# Neon_Fader_V2_v376.net
KiCad netlist of a schematic drawn in EAGLE
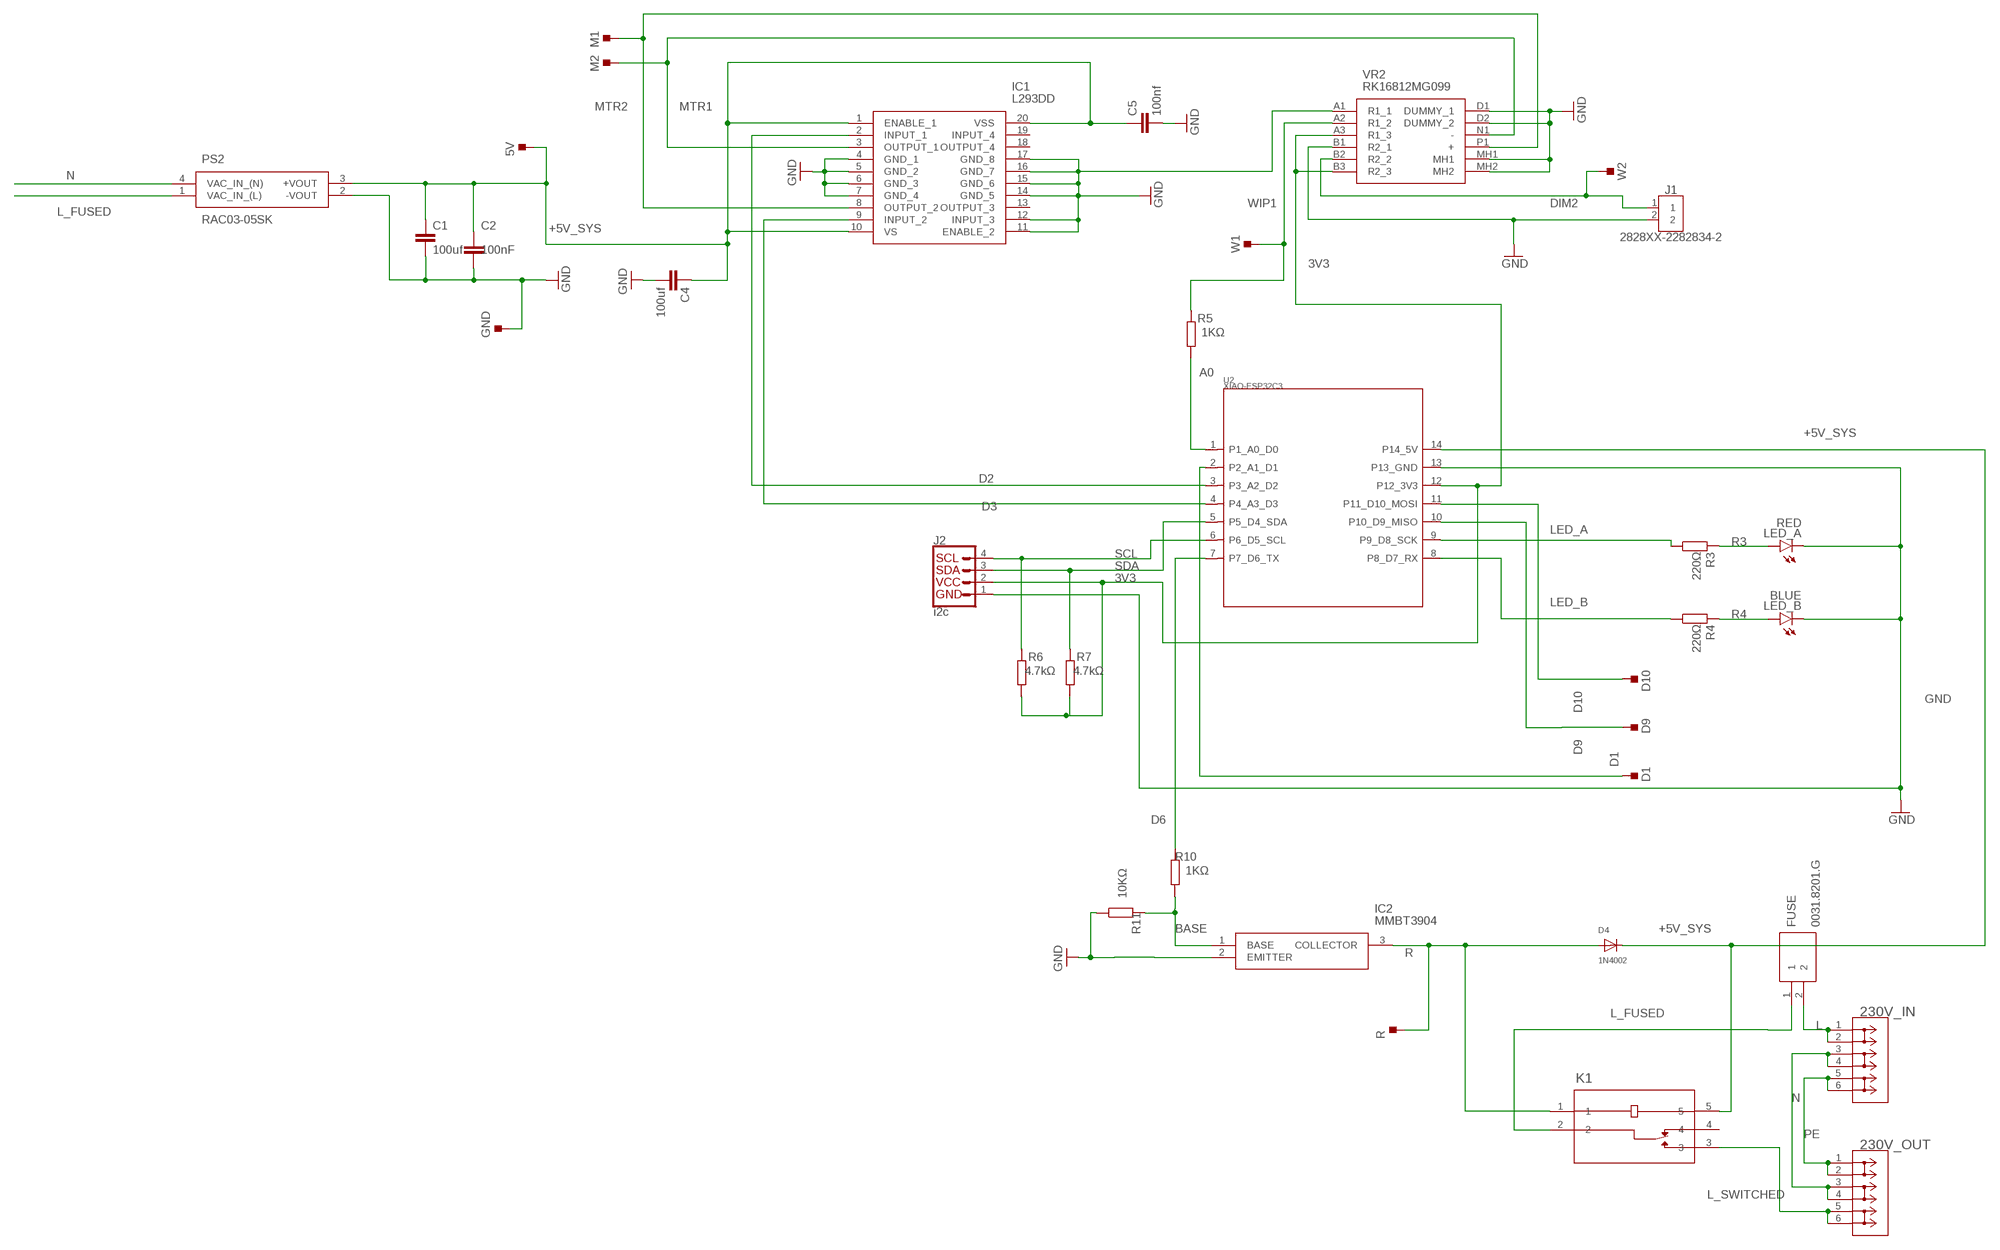
[diagram p0: schematic, sheet 1]

(export (version "E")
  (design (tool "Eeschema 10.0.6"))
  (components
    (comp (ref "5V")
      (value "TESTPOINT_TPS-PAD-036")
      (footprint "eagle-import:TESTPOINT_PAD-036")
      (libsource (lib "eagle-import") (part "TESTPOINT_TPS-PAD-036"))
    )
    (comp (ref "230V_IN")
      (value "2604-1103CONN3_2604-1103_WAG")
      (footprint "eagle-import:CONN3_2604-1103_WAG")
      (fields
        (field (name "MANUFACTURER_PART_NUMBER") "2604-1103")
        (field (name "COPYRIGHT") "Copyright (C) 2026 Ultra Librarian. All rights reserved.")
      )
      (libsource (lib "eagle-import") (part "2604-1103CONN3_2604-1103_WAG"))
    )
    (comp (ref "230V_OUT")
      (value "2604-1103CONN3_2604-1103_WAG")
      (footprint "eagle-import:CONN3_2604-1103_WAG")
      (fields
        (field (name "MANUFACTURER_PART_NUMBER") "2604-1103")
        (field (name "COPYRIGHT") "Copyright (C) 2026 Ultra Librarian. All rights reserved.")
      )
      (libsource (lib "eagle-import") (part "2604-1103CONN3_2604-1103_WAG"))
    )
    (comp (ref "C1")
      (value "100uf")
      (footprint "eagle-import:C1210")
      (libsource (lib "eagle-import") (part "C-EUC1210"))
    )
    (comp (ref "C2")
      (value "100nF")
      (footprint "eagle-import:C0402")
      (libsource (lib "eagle-import") (part "C-EUC0402"))
    )
    (comp (ref "C4")
      (value "100uf")
      (footprint "eagle-import:C1210")
      (libsource (lib "eagle-import") (part "C-EUC1210"))
    )
    (comp (ref "C5")
      (value "100nf")
      (footprint "eagle-import:C0402")
      (libsource (lib "eagle-import") (part "C-EUC0402"))
    )
    (comp (ref "D1")
      (value "TESTPOINT_TPS-PAD-036")
      (footprint "eagle-import:TESTPOINT_PAD-036")
      (libsource (lib "eagle-import") (part "TESTPOINT_TPS-PAD-036"))
    )
    (comp (ref "D4")
      (value "1N4002")
      (footprint "eagle-import:SOD-123")
      (libsource (lib "eagle-import") (part "DIODESOD-123"))
    )
    (comp (ref "D9")
      (value "TESTPOINT_TPS-PAD-036")
      (footprint "eagle-import:TESTPOINT_PAD-036")
      (libsource (lib "eagle-import") (part "TESTPOINT_TPS-PAD-036"))
    )
    (comp (ref "D10")
      (value "TESTPOINT_TPS-PAD-036")
      (footprint "eagle-import:TESTPOINT_PAD-036")
      (libsource (lib "eagle-import") (part "TESTPOINT_TPS-PAD-036"))
    )
    (comp (ref "FUSE")
      (value "0031.8201.G")
      (footprint "eagle-import:00318201G")
      (fields (field (name "MOUSER_PART_NUMBER") "693-0031.8201.G"))
      (libsource (lib "eagle-import") (part "0031.8201.G"))
    )
    (comp (ref "GND")
      (value "TESTPOINT_TPS-PAD-036")
      (footprint "eagle-import:TESTPOINT_PAD-036")
      (libsource (lib "eagle-import") (part "TESTPOINT_TPS-PAD-036"))
    )
    (comp (ref "IC1")
      (value "L293DD")
      (footprint "eagle-import:SOIC127P1032X265-20N")
      (fields (field (name "MOUSER_PART_NUMBER") "511-L293DD"))
      (libsource (lib "eagle-import") (part "L293DD"))
    )
    (comp (ref "IC2")
      (value "MMBT3904")
      (footprint "eagle-import:SOT95P240X110-3N")
      (fields (field (name "MOUSER_PART_NUMBER") "583-MMBT3904"))
      (libsource (lib "eagle-import") (part "MMBT3904"))
    )
    (comp (ref "J1")
      (value "2828XX-2282834-2")
      (footprint "eagle-import:TERMBLK_254-2N")
      (fields (field (name "MANUFACTURER") "TE Connectivity AMP Connectors") (field (name "MPN") "282834-2 "))
      (libsource (lib "eagle-import") (part "2828XX-2282834-2"))
    )
    (comp (ref "J2")
      (value "i2c")
      (footprint "eagle-import:1X04_1MM_RA")
      (libsource (lib "eagle-import") (part "QWIIC_CONNECTORJS-1MM"))
    )
    (comp (ref "K1")
      (value "G6RN-1_DC5RELAY_G6RN-1_OMR")
      (footprint "eagle-import:RELAY_G6RN-1_OMR")
      (fields
        (field (name "MANUFACTURER_PART_NUMBER") "G6RN-1 DC5")
        (field (name "COPYRIGHT") "Copyright (C) 2026 Ultra Librarian. All rights reserved.")
      )
      (libsource (lib "eagle-import") (part "G6RN-1_DC5RELAY_G6RN-1_OMR"))
    )
    (comp (ref "LED_A")
      (value "RED")
      (footprint "eagle-import:CHIPLED_1206")
      (libsource (lib "eagle-import") (part "LEDCHIPLED_1206"))
    )
    (comp (ref "LED_B")
      (value "BLUE")
      (footprint "eagle-import:CHIPLED_1206")
      (libsource (lib "eagle-import") (part "LEDCHIPLED_1206"))
    )
    (comp (ref "M1")
      (value "TESTPOINT_TPS-PAD-036")
      (footprint "eagle-import:TESTPOINT_PAD-036")
      (libsource (lib "eagle-import") (part "TESTPOINT_TPS-PAD-036"))
    )
    (comp (ref "M2")
      (value "TESTPOINT_TPS-PAD-036")
      (footprint "eagle-import:TESTPOINT_PAD-036")
      (libsource (lib "eagle-import") (part "TESTPOINT_TPS-PAD-036"))
    )
    (comp (ref "PS2")
      (value "RAC03-05SK")
      (footprint "eagle-import:RAC0305SK")
      (fields (field (name "MOUSER_PART_NUMBER") "919-RAC03-05SK"))
      (libsource (lib "eagle-import") (part "RAC03-05SK"))
    )
    (comp (ref "R")
      (value "TESTPOINT_TPS-PAD-036")
      (footprint "eagle-import:TESTPOINT_PAD-036")
      (libsource (lib "eagle-import") (part "TESTPOINT_TPS-PAD-036"))
    )
    (comp (ref "R3")
      (value "220Ω")
      (footprint "eagle-import:R0402")
      (libsource (lib "eagle-import") (part "R-EU_R0402"))
    )
    (comp (ref "R4")
      (value "220Ω")
      (footprint "eagle-import:R0402")
      (libsource (lib "eagle-import") (part "R-EU_R0402"))
    )
    (comp (ref "R5")
      (value "1KΩ")
      (footprint "eagle-import:R0402")
      (libsource (lib "eagle-import") (part "R-EU_R0402"))
    )
    (comp (ref "R6")
      (value "4.7kΩ")
      (footprint "eagle-import:R0402")
      (libsource (lib "eagle-import") (part "R-EU_R0402"))
    )
    (comp (ref "R7")
      (value "4.7kΩ")
      (footprint "eagle-import:R0402")
      (libsource (lib "eagle-import") (part "R-EU_R0402"))
    )
    (comp (ref "R10")
      (value "1KΩ")
      (footprint "eagle-import:R0402")
      (libsource (lib "eagle-import") (part "R-EU_R0402"))
    )
    (comp (ref "R11")
      (value "10KΩ")
      (footprint "eagle-import:R0402")
      (libsource (lib "eagle-import") (part "R-EU_R0402"))
    )
    (comp (ref "U2")
      (value "XIAO-ESP32C3")
      (footprint "eagle-import:XIAO-GENERIC-HYBRID-MODULE14P-2.54-21X17.8MM")
      (libsource (lib "eagle-import") (part "XIAO-THRUHOLEHYBRID-SMT-THT"))
    )
    (comp (ref "VR2")
      (value "RK16812MG099")
      (footprint "eagle-import:RK16812MG099")
      (fields (field (name "MOUSER_PART_NUMBER") "688-RK16812MG099"))
      (libsource (lib "eagle-import") (part "RK16812MG099"))
    )
    (comp (ref "W1")
      (value "TESTPOINT_TPS-PAD-036")
      (footprint "eagle-import:TESTPOINT_PAD-036")
      (libsource (lib "eagle-import") (part "TESTPOINT_TPS-PAD-036"))
    )
    (comp (ref "W2")
      (value "TESTPOINT_TPS-PAD-036")
      (footprint "eagle-import:TESTPOINT_PAD-036")
      (libsource (lib "eagle-import") (part "TESTPOINT_TPS-PAD-036"))
    )
  )
  (nets
    (net (code "1") (name "/+5V_SYS") (class "Default")
      (node (ref "5V") (pin "1") (pinfunction "TP_1") (pintype "passive"))
      (node (ref "C1") (pin "1") (pinfunction "1_1") (pintype "passive"))
      (node (ref "C2") (pin "1") (pinfunction "1_1") (pintype "passive"))
      (node (ref "C4") (pin "1") (pinfunction "1_1") (pintype "passive"))
      (node (ref "C5") (pin "1") (pinfunction "1_1") (pintype "passive"))
      (node (ref "D4") (pin "C") (pinfunction "C_C") (pintype "passive"))
      (node (ref "IC1") (pin "1") (pinfunction "ENABLE_1_1") (pintype "bidirectional"))
      (node (ref "IC1") (pin "10") (pinfunction "VS_10") (pintype "bidirectional"))
      (node (ref "IC1") (pin "20") (pinfunction "VSS_20") (pintype "bidirectional"))
      (node (ref "K1") (pin "5") (pinfunction "5_5") (pintype "passive"))
      (node (ref "PS2") (pin "3") (pinfunction "+VOUT_3") (pintype "bidirectional"))
      (node (ref "U2") (pin "14") (pinfunction "P14_5V_14") (pintype "bidirectional"))
    )
    (net (code "2") (name "/3V3") (class "Default")
      (node (ref "J2") (pin "2") (pinfunction "VCC_2") (pintype "power_in"))
      (node (ref "R6") (pin "1") (pinfunction "1_1") (pintype "passive"))
      (node (ref "R7") (pin "1") (pinfunction "1_1") (pintype "passive"))
      (node (ref "U2") (pin "12") (pinfunction "P12_3V3_12") (pintype "bidirectional"))
      (node (ref "VR2") (pin "A3") (pinfunction "R1_3_A3") (pintype "bidirectional"))
      (node (ref "VR2") (pin "B3") (pinfunction "R2_3_B3") (pintype "bidirectional"))
    )
    (net (code "3") (name "/A0") (class "Default")
      (node (ref "R5") (pin "1") (pinfunction "1_1") (pintype "passive"))
      (node (ref "U2") (pin "1") (pinfunction "P1_A0_D0_1") (pintype "bidirectional"))
    )
    (net (code "4") (name "/BASE") (class "Default")
      (node (ref "IC2") (pin "1") (pinfunction "BASE_1") (pintype "bidirectional"))
      (node (ref "R10") (pin "1") (pinfunction "1_1") (pintype "passive"))
      (node (ref "R11") (pin "2") (pinfunction "2_2") (pintype "passive"))
    )
    (net (code "5") (name "/D1") (class "Default")
      (node (ref "D1") (pin "1") (pinfunction "TP_1") (pintype "passive"))
      (node (ref "U2") (pin "2") (pinfunction "P2_A1_D1_2") (pintype "bidirectional"))
    )
    (net (code "6") (name "/D2") (class "Default")
      (node (ref "IC1") (pin "2") (pinfunction "INPUT_1_2") (pintype "bidirectional"))
      (node (ref "U2") (pin "3") (pinfunction "P3_A2_D2_3") (pintype "bidirectional"))
    )
    (net (code "7") (name "/D3") (class "Default")
      (node (ref "IC1") (pin "9") (pinfunction "INPUT_2_9") (pintype "bidirectional"))
      (node (ref "U2") (pin "4") (pinfunction "P4_A3_D3_4") (pintype "bidirectional"))
    )
    (net (code "8") (name "/D6") (class "Default")
      (node (ref "R10") (pin "2") (pinfunction "2_2") (pintype "passive"))
      (node (ref "U2") (pin "7") (pinfunction "P7_D6_TX_7") (pintype "bidirectional"))
    )
    (net (code "9") (name "/D9") (class "Default")
      (node (ref "D9") (pin "1") (pinfunction "TP_1") (pintype "passive"))
      (node (ref "U2") (pin "10") (pinfunction "P10_D9_MISO_10") (pintype "bidirectional"))
    )
    (net (code "10") (name "/D10") (class "Default")
      (node (ref "D10") (pin "1") (pinfunction "TP_1") (pintype "passive"))
      (node (ref "U2") (pin "11") (pinfunction "P11_D10_MOSI_11") (pintype "bidirectional"))
    )
    (net (code "11") (name "/DIM2") (class "Default")
      (node (ref "J1") (pin "1") (pinfunction "1_1") (pintype "bidirectional"))
      (node (ref "VR2") (pin "B2") (pinfunction "R2_2_B2") (pintype "bidirectional"))
      (node (ref "W2") (pin "1") (pinfunction "TP_1") (pintype "passive"))
    )
    (net (code "12") (name "/L") (class "Default")
      (node (ref "230V_IN") (pin "1") (pinfunction "1_1_1") (pintype "passive"))
      (node (ref "230V_IN") (pin "2") (pinfunction "1_2_2") (pintype "passive"))
      (node (ref "FUSE") (pin "2") (pinfunction "2_2") (pintype "bidirectional"))
    )
    (net (code "13") (name "/LED_A") (class "Default")
      (node (ref "R3") (pin "1") (pinfunction "1_1") (pintype "passive"))
      (node (ref "U2") (pin "9") (pinfunction "P9_D8_SCK_9") (pintype "bidirectional"))
    )
    (net (code "14") (name "/LED_B") (class "Default")
      (node (ref "R4") (pin "1") (pinfunction "1_1") (pintype "passive"))
      (node (ref "U2") (pin "8") (pinfunction "P8_D7_RX_8") (pintype "bidirectional"))
    )
    (net (code "15") (name "/L_FUSED") (class "Default")
      (node (ref "FUSE") (pin "1") (pinfunction "1_1") (pintype "bidirectional"))
      (node (ref "K1") (pin "2") (pinfunction "2_2") (pintype "passive"))
      (node (ref "PS2") (pin "1") (pinfunction "VAC_IN_(L)_1") (pintype "bidirectional"))
    )
    (net (code "16") (name "/L_SWITCHED") (class "Default")
      (node (ref "230V_OUT") (pin "5") (pinfunction "3_1_5") (pintype "passive"))
      (node (ref "230V_OUT") (pin "6") (pinfunction "3_2_6") (pintype "passive"))
      (node (ref "K1") (pin "3") (pinfunction "3_3") (pintype "passive"))
    )
    (net (code "17") (name "/MTR1") (class "Default")
      (node (ref "IC1") (pin "3") (pinfunction "OUTPUT_1_3") (pintype "bidirectional"))
      (node (ref "M2") (pin "1") (pinfunction "TP_1") (pintype "passive"))
      (node (ref "VR2") (pin "N1") (pinfunction "-_N1") (pintype "bidirectional"))
    )
    (net (code "18") (name "/MTR2") (class "Default")
      (node (ref "IC1") (pin "8") (pinfunction "OUTPUT_2_8") (pintype "bidirectional"))
      (node (ref "M1") (pin "1") (pinfunction "TP_1") (pintype "passive"))
      (node (ref "VR2") (pin "P1") (pinfunction "+_P1") (pintype "bidirectional"))
    )
    (net (code "19") (name "/N") (class "Default")
      (node (ref "230V_IN") (pin "3") (pinfunction "2_1_3") (pintype "passive"))
      (node (ref "230V_IN") (pin "4") (pinfunction "2_2_4") (pintype "passive"))
      (node (ref "230V_OUT") (pin "3") (pinfunction "2_1_3") (pintype "passive"))
      (node (ref "230V_OUT") (pin "4") (pinfunction "2_2_4") (pintype "passive"))
      (node (ref "PS2") (pin "4") (pinfunction "VAC_IN_(N)_4") (pintype "bidirectional"))
    )
    (net (code "20") (name "/PE") (class "Default")
      (node (ref "230V_IN") (pin "5") (pinfunction "3_1_5") (pintype "passive"))
      (node (ref "230V_IN") (pin "6") (pinfunction "3_2_6") (pintype "passive"))
      (node (ref "230V_OUT") (pin "1") (pinfunction "1_1_1") (pintype "passive"))
      (node (ref "230V_OUT") (pin "2") (pinfunction "1_2_2") (pintype "passive"))
    )
    (net (code "21") (name "/R") (class "Default")
      (node (ref "D4") (pin "A") (pinfunction "A_A") (pintype "passive"))
      (node (ref "IC2") (pin "3") (pinfunction "COLLECTOR_3") (pintype "bidirectional"))
      (node (ref "K1") (pin "1") (pinfunction "1_1") (pintype "passive"))
      (node (ref "R") (pin "1") (pinfunction "TP_1") (pintype "passive"))
    )
    (net (code "22") (name "/R3") (class "Default")
      (node (ref "LED_A") (pin "A") (pinfunction "A_A") (pintype "passive"))
      (node (ref "R3") (pin "2") (pinfunction "2_2") (pintype "passive"))
    )
    (net (code "23") (name "/R4") (class "Default")
      (node (ref "LED_B") (pin "A") (pinfunction "A_A") (pintype "passive"))
      (node (ref "R4") (pin "2") (pinfunction "2_2") (pintype "passive"))
    )
    (net (code "24") (name "/SCL") (class "Default")
      (node (ref "J2") (pin "4") (pinfunction "SCL_4") (pintype "passive"))
      (node (ref "R6") (pin "2") (pinfunction "2_2") (pintype "passive"))
      (node (ref "U2") (pin "6") (pinfunction "P6_D5_SCL_6") (pintype "bidirectional"))
    )
    (net (code "25") (name "/SDA") (class "Default")
      (node (ref "J2") (pin "3") (pinfunction "SDA_3") (pintype "passive"))
      (node (ref "R7") (pin "2") (pinfunction "2_2") (pintype "passive"))
      (node (ref "U2") (pin "5") (pinfunction "P5_D4_SDA_5") (pintype "bidirectional"))
    )
    (net (code "26") (name "/WIP1") (class "Default")
      (node (ref "R5") (pin "2") (pinfunction "2_2") (pintype "passive"))
      (node (ref "VR2") (pin "A2") (pinfunction "R1_2_A2") (pintype "bidirectional"))
      (node (ref "W1") (pin "1") (pinfunction "TP_1") (pintype "passive"))
    )
    (net (code "27") (name "GND") (class "Default")
      (node (ref "C1") (pin "2") (pinfunction "2_2") (pintype "passive"))
      (node (ref "C2") (pin "2") (pinfunction "2_2") (pintype "passive"))
      (node (ref "C4") (pin "2") (pinfunction "2_2") (pintype "passive"))
      (node (ref "C5") (pin "2") (pinfunction "2_2") (pintype "passive"))
      (node (ref "GND") (pin "1") (pinfunction "TP_1") (pintype "passive"))
      (node (ref "IC1") (pin "11") (pinfunction "ENABLE_2_11") (pintype "bidirectional"))
      (node (ref "IC1") (pin "12") (pinfunction "INPUT_3_12") (pintype "bidirectional"))
      (node (ref "IC1") (pin "14") (pinfunction "GND_5_14") (pintype "bidirectional"))
      (node (ref "IC1") (pin "15") (pinfunction "GND_6_15") (pintype "bidirectional"))
      (node (ref "IC1") (pin "16") (pinfunction "GND_7_16") (pintype "bidirectional"))
      (node (ref "IC1") (pin "17") (pinfunction "GND_8_17") (pintype "bidirectional"))
      (node (ref "IC1") (pin "4") (pinfunction "GND_1_4") (pintype "bidirectional"))
      (node (ref "IC1") (pin "5") (pinfunction "GND_2_5") (pintype "bidirectional"))
      (node (ref "IC1") (pin "6") (pinfunction "GND_3_6") (pintype "bidirectional"))
      (node (ref "IC1") (pin "7") (pinfunction "GND_4_7") (pintype "bidirectional"))
      (node (ref "IC2") (pin "2") (pinfunction "EMITTER_2") (pintype "bidirectional"))
      (node (ref "J1") (pin "2") (pinfunction "2_2") (pintype "bidirectional"))
      (node (ref "J2") (pin "1") (pinfunction "GND_1") (pintype "power_in"))
      (node (ref "LED_A") (pin "C") (pinfunction "C_C") (pintype "passive"))
      (node (ref "LED_B") (pin "C") (pinfunction "C_C") (pintype "passive"))
      (node (ref "PS2") (pin "2") (pinfunction "-VOUT_2") (pintype "bidirectional"))
      (node (ref "R11") (pin "1") (pinfunction "1_1") (pintype "passive"))
      (node (ref "U2") (pin "13") (pinfunction "P13_GND_13") (pintype "bidirectional"))
      (node (ref "VR2") (pin "A1") (pinfunction "R1_1_A1") (pintype "bidirectional"))
      (node (ref "VR2") (pin "B1") (pinfunction "R2_1_B1") (pintype "bidirectional"))
      (node (ref "VR2") (pin "D1") (pinfunction "DUMMY_1_D1") (pintype "bidirectional"))
      (node (ref "VR2") (pin "D2") (pinfunction "DUMMY_2_D2") (pintype "bidirectional"))
      (node (ref "VR2") (pin "MH1") (pinfunction "MH1_MH1") (pintype "bidirectional"))
      (node (ref "VR2") (pin "MH2") (pinfunction "MH2_MH2") (pintype "bidirectional"))
    )
    (net (code "28") (name "unconnected-(IC1-INPUT_4-Pad19)") (class "Default")
      (node (ref "IC1") (pin "19") (pinfunction "INPUT_4_19") (pintype "bidirectional"))
    )
    (net (code "29") (name "unconnected-(IC1-OUTPUT_3-Pad13)") (class "Default")
      (node (ref "IC1") (pin "13") (pinfunction "OUTPUT_3_13") (pintype "bidirectional"))
    )
    (net (code "30") (name "unconnected-(IC1-OUTPUT_4-Pad18)") (class "Default")
      (node (ref "IC1") (pin "18") (pinfunction "OUTPUT_4_18") (pintype "bidirectional"))
    )
    (net (code "31") (name "unconnected-(K1-Pad4)") (class "Default")
      (node (ref "K1") (pin "4") (pinfunction "4_4") (pintype "passive"))
    )
  )
)
